# untitled.net
KiCad netlist of a schematic drawn in EAGLE
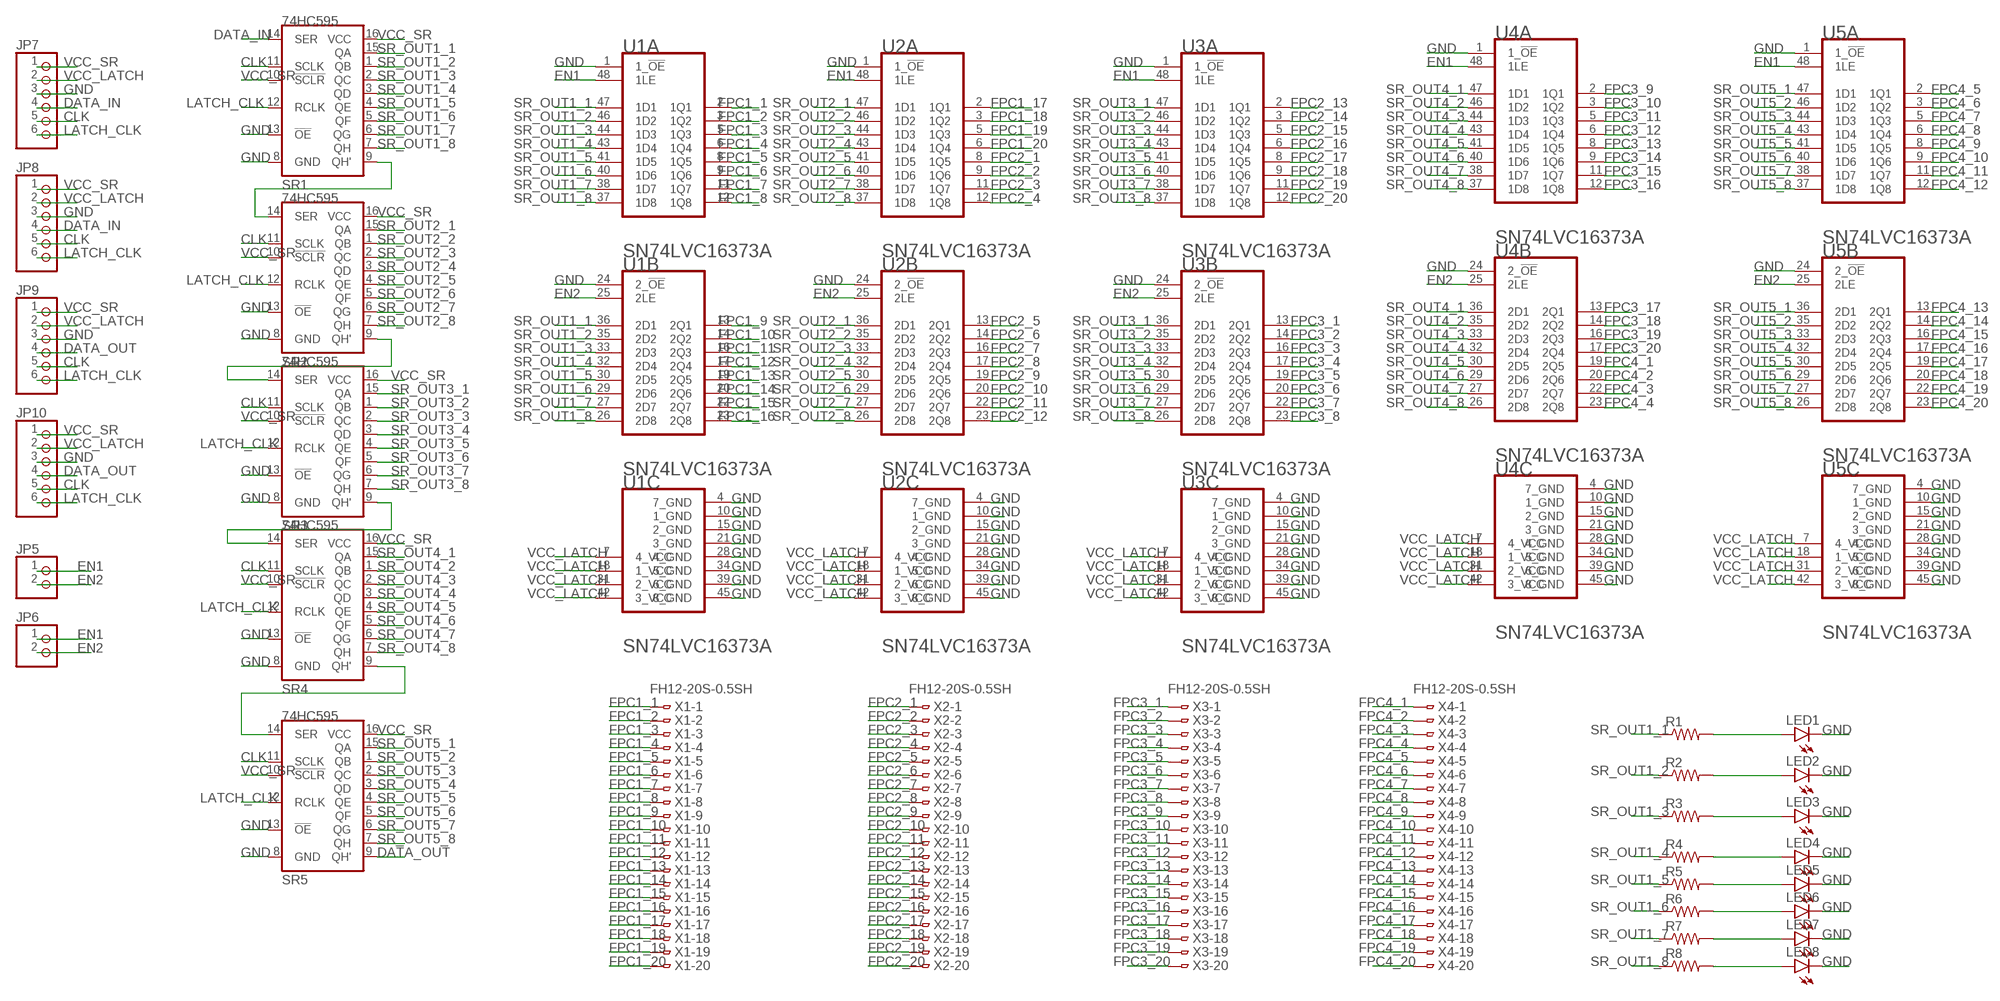
[diagram p0: schematic, sheet 1]

(export (version "E")
  (design (tool "Eeschema 10.0.6"))
  (components
    (comp (ref "JP5")
      (value "PINHD-1X2")
      (footprint "eagle-import:1X02")
      (libsource (lib "eagle-import") (part "PINHD-1X2"))
    )
    (comp (ref "JP6")
      (value "PINHD-1X2")
      (footprint "eagle-import:1X02")
      (libsource (lib "eagle-import") (part "PINHD-1X2"))
    )
    (comp (ref "JP7")
      (value "PINHD-1X6")
      (footprint "eagle-import:1X06")
      (libsource (lib "eagle-import") (part "PINHD-1X6"))
    )
    (comp (ref "JP8")
      (value "PINHD-1X6")
      (footprint "eagle-import:1X06")
      (libsource (lib "eagle-import") (part "PINHD-1X6"))
    )
    (comp (ref "JP9")
      (value "PINHD-1X6")
      (footprint "eagle-import:1X06")
      (libsource (lib "eagle-import") (part "PINHD-1X6"))
    )
    (comp (ref "JP10")
      (value "PINHD-1X6")
      (footprint "eagle-import:1X06")
      (libsource (lib "eagle-import") (part "PINHD-1X6"))
    )
    (comp (ref "LED1")
      (value "LEDCHIP-LED0805")
      (footprint "eagle-import:CHIP-LED0805")
      (libsource (lib "eagle-import") (part "LEDCHIP-LED0805"))
    )
    (comp (ref "LED2")
      (value "LEDCHIP-LED0805")
      (footprint "eagle-import:CHIP-LED0805")
      (libsource (lib "eagle-import") (part "LEDCHIP-LED0805"))
    )
    (comp (ref "LED3")
      (value "LEDCHIP-LED0805")
      (footprint "eagle-import:CHIP-LED0805")
      (libsource (lib "eagle-import") (part "LEDCHIP-LED0805"))
    )
    (comp (ref "LED4")
      (value "LEDCHIP-LED0805")
      (footprint "eagle-import:CHIP-LED0805")
      (libsource (lib "eagle-import") (part "LEDCHIP-LED0805"))
    )
    (comp (ref "LED5")
      (value "LEDCHIP-LED0805")
      (footprint "eagle-import:CHIP-LED0805")
      (libsource (lib "eagle-import") (part "LEDCHIP-LED0805"))
    )
    (comp (ref "LED6")
      (value "LEDCHIP-LED0805")
      (footprint "eagle-import:CHIP-LED0805")
      (libsource (lib "eagle-import") (part "LEDCHIP-LED0805"))
    )
    (comp (ref "LED7")
      (value "LEDCHIP-LED0805")
      (footprint "eagle-import:CHIP-LED0805")
      (libsource (lib "eagle-import") (part "LEDCHIP-LED0805"))
    )
    (comp (ref "LED8")
      (value "LEDCHIP-LED0805")
      (footprint "eagle-import:CHIP-LED0805")
      (libsource (lib "eagle-import") (part "LEDCHIP-LED0805"))
    )
    (comp (ref "R1")
      (value "R-US_R0805")
      (footprint "eagle-import:R0805")
      (libsource (lib "eagle-import") (part "R-US_R0805"))
    )
    (comp (ref "R2")
      (value "R-US_R0805")
      (footprint "eagle-import:R0805")
      (libsource (lib "eagle-import") (part "R-US_R0805"))
    )
    (comp (ref "R3")
      (value "R-US_R0805")
      (footprint "eagle-import:R0805")
      (libsource (lib "eagle-import") (part "R-US_R0805"))
    )
    (comp (ref "R4")
      (value "R-US_R0805")
      (footprint "eagle-import:R0805")
      (libsource (lib "eagle-import") (part "R-US_R0805"))
    )
    (comp (ref "R5")
      (value "R-US_R0805")
      (footprint "eagle-import:R0805")
      (libsource (lib "eagle-import") (part "R-US_R0805"))
    )
    (comp (ref "R6")
      (value "R-US_R0805")
      (footprint "eagle-import:R0805")
      (libsource (lib "eagle-import") (part "R-US_R0805"))
    )
    (comp (ref "R7")
      (value "R-US_R0805")
      (footprint "eagle-import:R0805")
      (libsource (lib "eagle-import") (part "R-US_R0805"))
    )
    (comp (ref "R8")
      (value "R-US_R0805")
      (footprint "eagle-import:R0805")
      (libsource (lib "eagle-import") (part "R-US_R0805"))
    )
    (comp (ref "SR1")
      (value "74HC595")
      (footprint "eagle-import:SO16")
      (fields (field (name "MF") "Nexperia"))
      (libsource (lib "eagle-import") (part "74HC595"))
    )
    (comp (ref "SR2")
      (value "74HC595")
      (footprint "eagle-import:SO16")
      (fields (field (name "MF") "Nexperia"))
      (libsource (lib "eagle-import") (part "74HC595"))
    )
    (comp (ref "SR3")
      (value "74HC595")
      (footprint "eagle-import:SO16")
      (fields (field (name "MF") "Nexperia"))
      (libsource (lib "eagle-import") (part "74HC595"))
    )
    (comp (ref "SR4")
      (value "74HC595")
      (footprint "eagle-import:SO16")
      (fields (field (name "MF") "Nexperia"))
      (libsource (lib "eagle-import") (part "74HC595"))
    )
    (comp (ref "SR5")
      (value "74HC595")
      (footprint "eagle-import:SO16")
      (fields (field (name "MF") "Nexperia"))
      (libsource (lib "eagle-import") (part "74HC595"))
    )
    (comp (ref "U1")
      (value "TEXAS_INSTRUMENTS_SN74LVC16373ATEXAS_INSTRUMENTS_SN74LVC16373A_0_2")
      (footprint "eagle-import:TEXAS_INSTRUMENTS_SN74LVC16373A_2")
      (fields (field (name "MF") "Texas Instruments") (field (name "MPN") "SN74LVC16373A"))
      (libsource (lib "eagle-import") (part "TEXAS_INSTRUMENTS_SN74LVC16373ATEXAS_INSTRUMENTS_SN74LVC16373A_0_2"))
    )
    (comp (ref "U2")
      (value "TEXAS_INSTRUMENTS_SN74LVC16373ATEXAS_INSTRUMENTS_SN74LVC16373A_0_2")
      (footprint "eagle-import:TEXAS_INSTRUMENTS_SN74LVC16373A_2")
      (fields (field (name "MF") "Texas Instruments") (field (name "MPN") "SN74LVC16373A"))
      (libsource (lib "eagle-import") (part "TEXAS_INSTRUMENTS_SN74LVC16373ATEXAS_INSTRUMENTS_SN74LVC16373A_0_2"))
    )
    (comp (ref "U3")
      (value "TEXAS_INSTRUMENTS_SN74LVC16373ATEXAS_INSTRUMENTS_SN74LVC16373A_0_2")
      (footprint "eagle-import:TEXAS_INSTRUMENTS_SN74LVC16373A_2")
      (fields (field (name "MF") "Texas Instruments") (field (name "MPN") "SN74LVC16373A"))
      (libsource (lib "eagle-import") (part "TEXAS_INSTRUMENTS_SN74LVC16373ATEXAS_INSTRUMENTS_SN74LVC16373A_0_2"))
    )
    (comp (ref "U4")
      (value "TEXAS_INSTRUMENTS_SN74LVC16373ATEXAS_INSTRUMENTS_SN74LVC16373A_0_2")
      (footprint "eagle-import:TEXAS_INSTRUMENTS_SN74LVC16373A_2")
      (fields (field (name "MF") "Texas Instruments") (field (name "MPN") "SN74LVC16373A"))
      (libsource (lib "eagle-import") (part "TEXAS_INSTRUMENTS_SN74LVC16373ATEXAS_INSTRUMENTS_SN74LVC16373A_0_2"))
    )
    (comp (ref "U5")
      (value "TEXAS_INSTRUMENTS_SN74LVC16373ATEXAS_INSTRUMENTS_SN74LVC16373A_0_2")
      (footprint "eagle-import:TEXAS_INSTRUMENTS_SN74LVC16373A_2")
      (fields (field (name "MF") "Texas Instruments") (field (name "MPN") "SN74LVC16373A"))
      (libsource (lib "eagle-import") (part "TEXAS_INSTRUMENTS_SN74LVC16373ATEXAS_INSTRUMENTS_SN74LVC16373A_0_2"))
    )
    (comp (ref "X1")
      (value "FH12-20S-0.5SH")
      (footprint "eagle-import:FH12-20S-0.5SH")
      (fields (field (name "MPN") "FH12-20S-0.5SH(55)"))
      (libsource (lib "eagle-import") (part "FH12-20S-0.5SH"))
    )
    (comp (ref "X2")
      (value "FH12-20S-0.5SH")
      (footprint "eagle-import:FH12-20S-0.5SH")
      (fields (field (name "MPN") "FH12-20S-0.5SH(55)"))
      (libsource (lib "eagle-import") (part "FH12-20S-0.5SH"))
    )
    (comp (ref "X3")
      (value "FH12-20S-0.5SH")
      (footprint "eagle-import:FH12-20S-0.5SH")
      (fields (field (name "MPN") "FH12-20S-0.5SH(55)"))
      (libsource (lib "eagle-import") (part "FH12-20S-0.5SH"))
    )
    (comp (ref "X4")
      (value "FH12-20S-0.5SH")
      (footprint "eagle-import:FH12-20S-0.5SH")
      (fields (field (name "MPN") "FH12-20S-0.5SH(55)"))
      (libsource (lib "eagle-import") (part "FH12-20S-0.5SH"))
    )
  )
  (nets
    (net (code "1") (name "/CLK") (class "Default")
      (node (ref "JP10") (pin "5") (pinfunction "5_5") (pintype "passive"))
      (node (ref "JP7") (pin "5") (pinfunction "5_5") (pintype "passive"))
      (node (ref "JP8") (pin "5") (pinfunction "5_5") (pintype "passive"))
      (node (ref "JP9") (pin "5") (pinfunction "5_5") (pintype "passive"))
      (node (ref "SR1") (pin "11") (pinfunction "SCLK_11") (pintype "input"))
      (node (ref "SR2") (pin "11") (pinfunction "SCLK_11") (pintype "input"))
      (node (ref "SR3") (pin "11") (pinfunction "SCLK_11") (pintype "input"))
      (node (ref "SR4") (pin "11") (pinfunction "SCLK_11") (pintype "input"))
      (node (ref "SR5") (pin "11") (pinfunction "SCLK_11") (pintype "input"))
    )
    (net (code "2") (name "/DATA_IN") (class "Default")
      (node (ref "JP7") (pin "4") (pinfunction "4_4") (pintype "passive"))
      (node (ref "JP8") (pin "4") (pinfunction "4_4") (pintype "passive"))
      (node (ref "SR1") (pin "14") (pinfunction "SER_14") (pintype "input"))
    )
    (net (code "3") (name "/DATA_OUT") (class "Default")
      (node (ref "JP10") (pin "4") (pinfunction "4_4") (pintype "passive"))
      (node (ref "JP9") (pin "4") (pinfunction "4_4") (pintype "passive"))
      (node (ref "SR5") (pin "9") (pinfunction "QH'_9") (pintype "tri_state"))
    )
    (net (code "4") (name "/EN1") (class "Default")
      (node (ref "JP5") (pin "1") (pinfunction "1_1") (pintype "passive"))
      (node (ref "JP6") (pin "1") (pinfunction "1_1") (pintype "passive"))
      (node (ref "U1") (pin "48") (pinfunction "1LE_48") (pintype "input"))
      (node (ref "U2") (pin "48") (pinfunction "1LE_48") (pintype "input"))
      (node (ref "U3") (pin "48") (pinfunction "1LE_48") (pintype "input"))
      (node (ref "U4") (pin "48") (pinfunction "1LE_48") (pintype "input"))
      (node (ref "U5") (pin "48") (pinfunction "1LE_48") (pintype "input"))
    )
    (net (code "5") (name "/EN2") (class "Default")
      (node (ref "JP5") (pin "2") (pinfunction "2_2") (pintype "passive"))
      (node (ref "JP6") (pin "2") (pinfunction "2_2") (pintype "passive"))
      (node (ref "U1") (pin "25") (pinfunction "2LE_25") (pintype "input"))
      (node (ref "U2") (pin "25") (pinfunction "2LE_25") (pintype "input"))
      (node (ref "U3") (pin "25") (pinfunction "2LE_25") (pintype "input"))
      (node (ref "U4") (pin "25") (pinfunction "2LE_25") (pintype "input"))
      (node (ref "U5") (pin "25") (pinfunction "2LE_25") (pintype "input"))
    )
    (net (code "6") (name "/FPC1_1") (class "Default")
      (node (ref "U1") (pin "2") (pinfunction "1Q1_2") (pintype "tri_state"))
      (node (ref "X1") (pin "1") (pinfunction "1_1") (pintype "passive"))
    )
    (net (code "7") (name "/FPC1_2") (class "Default")
      (node (ref "U1") (pin "3") (pinfunction "1Q2_3") (pintype "tri_state"))
      (node (ref "X1") (pin "2") (pinfunction "1_2") (pintype "passive"))
    )
    (net (code "8") (name "/FPC1_3") (class "Default")
      (node (ref "U1") (pin "5") (pinfunction "1Q3_5") (pintype "tri_state"))
      (node (ref "X1") (pin "3") (pinfunction "1_3") (pintype "passive"))
    )
    (net (code "9") (name "/FPC1_4") (class "Default")
      (node (ref "U1") (pin "6") (pinfunction "1Q4_6") (pintype "tri_state"))
      (node (ref "X1") (pin "4") (pinfunction "1_4") (pintype "passive"))
    )
    (net (code "10") (name "/FPC1_5") (class "Default")
      (node (ref "U1") (pin "8") (pinfunction "1Q5_8") (pintype "tri_state"))
      (node (ref "X1") (pin "5") (pinfunction "1_5") (pintype "passive"))
    )
    (net (code "11") (name "/FPC1_6") (class "Default")
      (node (ref "U1") (pin "9") (pinfunction "1Q6_9") (pintype "tri_state"))
      (node (ref "X1") (pin "6") (pinfunction "1_6") (pintype "passive"))
    )
    (net (code "12") (name "/FPC1_7") (class "Default")
      (node (ref "U1") (pin "11") (pinfunction "1Q7_11") (pintype "tri_state"))
      (node (ref "X1") (pin "7") (pinfunction "1_7") (pintype "passive"))
    )
    (net (code "13") (name "/FPC1_8") (class "Default")
      (node (ref "U1") (pin "12") (pinfunction "1Q8_12") (pintype "tri_state"))
      (node (ref "X1") (pin "8") (pinfunction "1_8") (pintype "passive"))
    )
    (net (code "14") (name "/FPC1_9") (class "Default")
      (node (ref "U1") (pin "13") (pinfunction "2Q1_13") (pintype "tri_state"))
      (node (ref "X1") (pin "9") (pinfunction "1_9") (pintype "passive"))
    )
    (net (code "15") (name "/FPC1_10") (class "Default")
      (node (ref "U1") (pin "14") (pinfunction "2Q2_14") (pintype "tri_state"))
      (node (ref "X1") (pin "10") (pinfunction "1_10") (pintype "passive"))
    )
    (net (code "16") (name "/FPC1_11") (class "Default")
      (node (ref "U1") (pin "16") (pinfunction "2Q3_16") (pintype "tri_state"))
      (node (ref "X1") (pin "11") (pinfunction "1_11") (pintype "passive"))
    )
    (net (code "17") (name "/FPC1_12") (class "Default")
      (node (ref "U1") (pin "17") (pinfunction "2Q4_17") (pintype "tri_state"))
      (node (ref "X1") (pin "12") (pinfunction "1_12") (pintype "passive"))
    )
    (net (code "18") (name "/FPC1_13") (class "Default")
      (node (ref "U1") (pin "19") (pinfunction "2Q5_19") (pintype "tri_state"))
      (node (ref "X1") (pin "13") (pinfunction "1_13") (pintype "passive"))
    )
    (net (code "19") (name "/FPC1_14") (class "Default")
      (node (ref "U1") (pin "20") (pinfunction "2Q6_20") (pintype "tri_state"))
      (node (ref "X1") (pin "14") (pinfunction "1_14") (pintype "passive"))
    )
    (net (code "20") (name "/FPC1_15") (class "Default")
      (node (ref "U1") (pin "22") (pinfunction "2Q7_22") (pintype "tri_state"))
      (node (ref "X1") (pin "15") (pinfunction "1_15") (pintype "passive"))
    )
    (net (code "21") (name "/FPC1_16") (class "Default")
      (node (ref "U1") (pin "23") (pinfunction "2Q8_23") (pintype "tri_state"))
      (node (ref "X1") (pin "16") (pinfunction "1_16") (pintype "passive"))
    )
    (net (code "22") (name "/FPC1_17") (class "Default")
      (node (ref "U2") (pin "2") (pinfunction "1Q1_2") (pintype "tri_state"))
      (node (ref "X1") (pin "17") (pinfunction "1_17") (pintype "passive"))
    )
    (net (code "23") (name "/FPC1_18") (class "Default")
      (node (ref "U2") (pin "3") (pinfunction "1Q2_3") (pintype "tri_state"))
      (node (ref "X1") (pin "18") (pinfunction "1_18") (pintype "passive"))
    )
    (net (code "24") (name "/FPC1_19") (class "Default")
      (node (ref "U2") (pin "5") (pinfunction "1Q3_5") (pintype "tri_state"))
      (node (ref "X1") (pin "19") (pinfunction "1_19") (pintype "passive"))
    )
    (net (code "25") (name "/FPC1_20") (class "Default")
      (node (ref "U2") (pin "6") (pinfunction "1Q4_6") (pintype "tri_state"))
      (node (ref "X1") (pin "20") (pinfunction "1_20") (pintype "passive"))
    )
    (net (code "26") (name "/FPC2_1") (class "Default")
      (node (ref "U2") (pin "8") (pinfunction "1Q5_8") (pintype "tri_state"))
      (node (ref "X2") (pin "1") (pinfunction "1_1") (pintype "passive"))
    )
    (net (code "27") (name "/FPC2_2") (class "Default")
      (node (ref "U2") (pin "9") (pinfunction "1Q6_9") (pintype "tri_state"))
      (node (ref "X2") (pin "2") (pinfunction "1_2") (pintype "passive"))
    )
    (net (code "28") (name "/FPC2_3") (class "Default")
      (node (ref "U2") (pin "11") (pinfunction "1Q7_11") (pintype "tri_state"))
      (node (ref "X2") (pin "3") (pinfunction "1_3") (pintype "passive"))
    )
    (net (code "29") (name "/FPC2_4") (class "Default")
      (node (ref "U2") (pin "12") (pinfunction "1Q8_12") (pintype "tri_state"))
      (node (ref "X2") (pin "4") (pinfunction "1_4") (pintype "passive"))
    )
    (net (code "30") (name "/FPC2_5") (class "Default")
      (node (ref "U2") (pin "13") (pinfunction "2Q1_13") (pintype "tri_state"))
      (node (ref "X2") (pin "5") (pinfunction "1_5") (pintype "passive"))
    )
    (net (code "31") (name "/FPC2_6") (class "Default")
      (node (ref "U2") (pin "14") (pinfunction "2Q2_14") (pintype "tri_state"))
      (node (ref "X2") (pin "6") (pinfunction "1_6") (pintype "passive"))
    )
    (net (code "32") (name "/FPC2_7") (class "Default")
      (node (ref "U2") (pin "16") (pinfunction "2Q3_16") (pintype "tri_state"))
      (node (ref "X2") (pin "7") (pinfunction "1_7") (pintype "passive"))
    )
    (net (code "33") (name "/FPC2_8") (class "Default")
      (node (ref "U2") (pin "17") (pinfunction "2Q4_17") (pintype "tri_state"))
      (node (ref "X2") (pin "8") (pinfunction "1_8") (pintype "passive"))
    )
    (net (code "34") (name "/FPC2_9") (class "Default")
      (node (ref "U2") (pin "19") (pinfunction "2Q5_19") (pintype "tri_state"))
      (node (ref "X2") (pin "9") (pinfunction "1_9") (pintype "passive"))
    )
    (net (code "35") (name "/FPC2_10") (class "Default")
      (node (ref "U2") (pin "20") (pinfunction "2Q6_20") (pintype "tri_state"))
      (node (ref "X2") (pin "10") (pinfunction "1_10") (pintype "passive"))
    )
    (net (code "36") (name "/FPC2_11") (class "Default")
      (node (ref "U2") (pin "22") (pinfunction "2Q7_22") (pintype "tri_state"))
      (node (ref "X2") (pin "11") (pinfunction "1_11") (pintype "passive"))
    )
    (net (code "37") (name "/FPC2_12") (class "Default")
      (node (ref "U2") (pin "23") (pinfunction "2Q8_23") (pintype "tri_state"))
      (node (ref "X2") (pin "12") (pinfunction "1_12") (pintype "passive"))
    )
    (net (code "38") (name "/FPC2_13") (class "Default")
      (node (ref "U3") (pin "2") (pinfunction "1Q1_2") (pintype "tri_state"))
      (node (ref "X2") (pin "13") (pinfunction "1_13") (pintype "passive"))
    )
    (net (code "39") (name "/FPC2_14") (class "Default")
      (node (ref "U3") (pin "3") (pinfunction "1Q2_3") (pintype "tri_state"))
      (node (ref "X2") (pin "14") (pinfunction "1_14") (pintype "passive"))
    )
    (net (code "40") (name "/FPC2_15") (class "Default")
      (node (ref "U3") (pin "5") (pinfunction "1Q3_5") (pintype "tri_state"))
      (node (ref "X2") (pin "15") (pinfunction "1_15") (pintype "passive"))
    )
    (net (code "41") (name "/FPC2_16") (class "Default")
      (node (ref "U3") (pin "6") (pinfunction "1Q4_6") (pintype "tri_state"))
      (node (ref "X2") (pin "16") (pinfunction "1_16") (pintype "passive"))
    )
    (net (code "42") (name "/FPC2_17") (class "Default")
      (node (ref "U3") (pin "8") (pinfunction "1Q5_8") (pintype "tri_state"))
      (node (ref "X2") (pin "17") (pinfunction "1_17") (pintype "passive"))
    )
    (net (code "43") (name "/FPC2_18") (class "Default")
      (node (ref "U3") (pin "9") (pinfunction "1Q6_9") (pintype "tri_state"))
      (node (ref "X2") (pin "18") (pinfunction "1_18") (pintype "passive"))
    )
    (net (code "44") (name "/FPC2_19") (class "Default")
      (node (ref "U3") (pin "11") (pinfunction "1Q7_11") (pintype "tri_state"))
      (node (ref "X2") (pin "19") (pinfunction "1_19") (pintype "passive"))
    )
    (net (code "45") (name "/FPC2_20") (class "Default")
      (node (ref "U3") (pin "12") (pinfunction "1Q8_12") (pintype "tri_state"))
      (node (ref "X2") (pin "20") (pinfunction "1_20") (pintype "passive"))
    )
    (net (code "46") (name "/FPC3_1") (class "Default")
      (node (ref "U3") (pin "13") (pinfunction "2Q1_13") (pintype "tri_state"))
      (node (ref "X3") (pin "1") (pinfunction "1_1") (pintype "passive"))
    )
    (net (code "47") (name "/FPC3_2") (class "Default")
      (node (ref "U3") (pin "14") (pinfunction "2Q2_14") (pintype "tri_state"))
      (node (ref "X3") (pin "2") (pinfunction "1_2") (pintype "passive"))
    )
    (net (code "48") (name "/FPC3_3") (class "Default")
      (node (ref "U3") (pin "16") (pinfunction "2Q3_16") (pintype "tri_state"))
      (node (ref "X3") (pin "3") (pinfunction "1_3") (pintype "passive"))
    )
    (net (code "49") (name "/FPC3_4") (class "Default")
      (node (ref "U3") (pin "17") (pinfunction "2Q4_17") (pintype "tri_state"))
      (node (ref "X3") (pin "4") (pinfunction "1_4") (pintype "passive"))
    )
    (net (code "50") (name "/FPC3_5") (class "Default")
      (node (ref "U3") (pin "19") (pinfunction "2Q5_19") (pintype "tri_state"))
      (node (ref "X3") (pin "5") (pinfunction "1_5") (pintype "passive"))
    )
    (net (code "51") (name "/FPC3_6") (class "Default")
      (node (ref "U3") (pin "20") (pinfunction "2Q6_20") (pintype "tri_state"))
      (node (ref "X3") (pin "6") (pinfunction "1_6") (pintype "passive"))
    )
    (net (code "52") (name "/FPC3_7") (class "Default")
      (node (ref "U3") (pin "22") (pinfunction "2Q7_22") (pintype "tri_state"))
      (node (ref "X3") (pin "7") (pinfunction "1_7") (pintype "passive"))
    )
    (net (code "53") (name "/FPC3_8") (class "Default")
      (node (ref "U3") (pin "23") (pinfunction "2Q8_23") (pintype "tri_state"))
      (node (ref "X3") (pin "8") (pinfunction "1_8") (pintype "passive"))
    )
    (net (code "54") (name "/FPC3_9") (class "Default")
      (node (ref "U4") (pin "2") (pinfunction "1Q1_2") (pintype "tri_state"))
      (node (ref "X3") (pin "9") (pinfunction "1_9") (pintype "passive"))
    )
    (net (code "55") (name "/FPC3_10") (class "Default")
      (node (ref "U4") (pin "3") (pinfunction "1Q2_3") (pintype "tri_state"))
      (node (ref "X3") (pin "10") (pinfunction "1_10") (pintype "passive"))
    )
    (net (code "56") (name "/FPC3_11") (class "Default")
      (node (ref "U4") (pin "5") (pinfunction "1Q3_5") (pintype "tri_state"))
      (node (ref "X3") (pin "11") (pinfunction "1_11") (pintype "passive"))
    )
    (net (code "57") (name "/FPC3_12") (class "Default")
      (node (ref "U4") (pin "6") (pinfunction "1Q4_6") (pintype "tri_state"))
      (node (ref "X3") (pin "12") (pinfunction "1_12") (pintype "passive"))
    )
    (net (code "58") (name "/FPC3_13") (class "Default")
      (node (ref "U4") (pin "8") (pinfunction "1Q5_8") (pintype "tri_state"))
      (node (ref "X3") (pin "13") (pinfunction "1_13") (pintype "passive"))
    )
    (net (code "59") (name "/FPC3_14") (class "Default")
      (node (ref "U4") (pin "9") (pinfunction "1Q6_9") (pintype "tri_state"))
      (node (ref "X3") (pin "14") (pinfunction "1_14") (pintype "passive"))
    )
    (net (code "60") (name "/FPC3_15") (class "Default")
      (node (ref "U4") (pin "11") (pinfunction "1Q7_11") (pintype "tri_state"))
      (node (ref "X3") (pin "15") (pinfunction "1_15") (pintype "passive"))
    )
    (net (code "61") (name "/FPC3_16") (class "Default")
      (node (ref "U4") (pin "12") (pinfunction "1Q8_12") (pintype "tri_state"))
      (node (ref "X3") (pin "16") (pinfunction "1_16") (pintype "passive"))
    )
    (net (code "62") (name "/FPC3_17") (class "Default")
      (node (ref "U4") (pin "13") (pinfunction "2Q1_13") (pintype "tri_state"))
      (node (ref "X3") (pin "17") (pinfunction "1_17") (pintype "passive"))
    )
    (net (code "63") (name "/FPC3_18") (class "Default")
      (node (ref "U4") (pin "14") (pinfunction "2Q2_14") (pintype "tri_state"))
      (node (ref "X3") (pin "18") (pinfunction "1_18") (pintype "passive"))
    )
    (net (code "64") (name "/FPC3_19") (class "Default")
      (node (ref "U4") (pin "16") (pinfunction "2Q3_16") (pintype "tri_state"))
      (node (ref "X3") (pin "19") (pinfunction "1_19") (pintype "passive"))
    )
    (net (code "65") (name "/FPC3_20") (class "Default")
      (node (ref "U4") (pin "17") (pinfunction "2Q4_17") (pintype "tri_state"))
      (node (ref "X3") (pin "20") (pinfunction "1_20") (pintype "passive"))
    )
    (net (code "66") (name "/FPC4_1") (class "Default")
      (node (ref "U4") (pin "19") (pinfunction "2Q5_19") (pintype "tri_state"))
      (node (ref "X4") (pin "1") (pinfunction "1_1") (pintype "passive"))
    )
    (net (code "67") (name "/FPC4_2") (class "Default")
      (node (ref "U4") (pin "20") (pinfunction "2Q6_20") (pintype "tri_state"))
      (node (ref "X4") (pin "2") (pinfunction "1_2") (pintype "passive"))
    )
    (net (code "68") (name "/FPC4_3") (class "Default")
      (node (ref "U4") (pin "22") (pinfunction "2Q7_22") (pintype "tri_state"))
      (node (ref "X4") (pin "3") (pinfunction "1_3") (pintype "passive"))
    )
    (net (code "69") (name "/FPC4_4") (class "Default")
      (node (ref "U4") (pin "23") (pinfunction "2Q8_23") (pintype "tri_state"))
      (node (ref "X4") (pin "4") (pinfunction "1_4") (pintype "passive"))
    )
    (net (code "70") (name "/FPC4_5") (class "Default")
      (node (ref "U5") (pin "2") (pinfunction "1Q1_2") (pintype "tri_state"))
      (node (ref "X4") (pin "5") (pinfunction "1_5") (pintype "passive"))
    )
    (net (code "71") (name "/FPC4_6") (class "Default")
      (node (ref "U5") (pin "3") (pinfunction "1Q2_3") (pintype "tri_state"))
      (node (ref "X4") (pin "6") (pinfunction "1_6") (pintype "passive"))
    )
    (net (code "72") (name "/FPC4_7") (class "Default")
      (node (ref "U5") (pin "5") (pinfunction "1Q3_5") (pintype "tri_state"))
      (node (ref "X4") (pin "7") (pinfunction "1_7") (pintype "passive"))
    )
    (net (code "73") (name "/FPC4_8") (class "Default")
      (node (ref "U5") (pin "6") (pinfunction "1Q4_6") (pintype "tri_state"))
      (node (ref "X4") (pin "8") (pinfunction "1_8") (pintype "passive"))
    )
    (net (code "74") (name "/FPC4_9") (class "Default")
      (node (ref "U5") (pin "8") (pinfunction "1Q5_8") (pintype "tri_state"))
      (node (ref "X4") (pin "9") (pinfunction "1_9") (pintype "passive"))
    )
    (net (code "75") (name "/FPC4_10") (class "Default")
      (node (ref "U5") (pin "9") (pinfunction "1Q6_9") (pintype "tri_state"))
      (node (ref "X4") (pin "10") (pinfunction "1_10") (pintype "passive"))
    )
    (net (code "76") (name "/FPC4_11") (class "Default")
      (node (ref "U5") (pin "11") (pinfunction "1Q7_11") (pintype "tri_state"))
      (node (ref "X4") (pin "11") (pinfunction "1_11") (pintype "passive"))
    )
    (net (code "77") (name "/FPC4_12") (class "Default")
      (node (ref "U5") (pin "12") (pinfunction "1Q8_12") (pintype "tri_state"))
      (node (ref "X4") (pin "12") (pinfunction "1_12") (pintype "passive"))
    )
    (net (code "78") (name "/FPC4_13") (class "Default")
      (node (ref "U5") (pin "13") (pinfunction "2Q1_13") (pintype "tri_state"))
      (node (ref "X4") (pin "13") (pinfunction "1_13") (pintype "passive"))
    )
    (net (code "79") (name "/FPC4_14") (class "Default")
      (node (ref "U5") (pin "14") (pinfunction "2Q2_14") (pintype "tri_state"))
      (node (ref "X4") (pin "14") (pinfunction "1_14") (pintype "passive"))
    )
    (net (code "80") (name "/FPC4_15") (class "Default")
      (node (ref "U5") (pin "16") (pinfunction "2Q3_16") (pintype "tri_state"))
      (node (ref "X4") (pin "15") (pinfunction "1_15") (pintype "passive"))
    )
    (net (code "81") (name "/FPC4_16") (class "Default")
      (node (ref "U5") (pin "17") (pinfunction "2Q4_17") (pintype "tri_state"))
      (node (ref "X4") (pin "16") (pinfunction "1_16") (pintype "passive"))
    )
    (net (code "82") (name "/FPC4_17") (class "Default")
      (node (ref "U5") (pin "19") (pinfunction "2Q5_19") (pintype "tri_state"))
      (node (ref "X4") (pin "17") (pinfunction "1_17") (pintype "passive"))
    )
    (net (code "83") (name "/FPC4_18") (class "Default")
      (node (ref "U5") (pin "20") (pinfunction "2Q6_20") (pintype "tri_state"))
      (node (ref "X4") (pin "18") (pinfunction "1_18") (pintype "passive"))
    )
    (net (code "84") (name "/FPC4_19") (class "Default")
      (node (ref "U5") (pin "22") (pinfunction "2Q7_22") (pintype "tri_state"))
      (node (ref "X4") (pin "19") (pinfunction "1_19") (pintype "passive"))
    )
    (net (code "85") (name "/FPC4_20") (class "Default")
      (node (ref "U5") (pin "23") (pinfunction "2Q8_23") (pintype "tri_state"))
      (node (ref "X4") (pin "20") (pinfunction "1_20") (pintype "passive"))
    )
    (net (code "86") (name "/GND") (class "Default")
      (node (ref "JP10") (pin "3") (pinfunction "3_3") (pintype "passive"))
      (node (ref "JP7") (pin "3") (pinfunction "3_3") (pintype "passive"))
      (node (ref "JP8") (pin "3") (pinfunction "3_3") (pintype "passive"))
      (node (ref "JP9") (pin "3") (pinfunction "3_3") (pintype "passive"))
      (node (ref "LED1") (pin "C") (pinfunction "C_C") (pintype "passive"))
      (node (ref "LED2") (pin "C") (pinfunction "C_C") (pintype "passive"))
      (node (ref "LED3") (pin "C") (pinfunction "C_C") (pintype "passive"))
      (node (ref "LED4") (pin "C") (pinfunction "C_C") (pintype "passive"))
      (node (ref "LED5") (pin "C") (pinfunction "C_C") (pintype "passive"))
      (node (ref "LED6") (pin "C") (pinfunction "C_C") (pintype "passive"))
      (node (ref "LED7") (pin "C") (pinfunction "C_C") (pintype "passive"))
      (node (ref "LED8") (pin "C") (pinfunction "C_C") (pintype "passive"))
      (node (ref "SR1") (pin "13") (pinfunction "~{OE}_13") (pintype "input"))
      (node (ref "SR1") (pin "8") (pinfunction "GND_8") (pintype "power_in"))
      (node (ref "SR2") (pin "13") (pinfunction "~{OE}_13") (pintype "input"))
      (node (ref "SR2") (pin "8") (pinfunction "GND_8") (pintype "power_in"))
      (node (ref "SR3") (pin "13") (pinfunction "~{OE}_13") (pintype "input"))
      (node (ref "SR3") (pin "8") (pinfunction "GND_8") (pintype "power_in"))
      (node (ref "SR4") (pin "13") (pinfunction "~{OE}_13") (pintype "input"))
      (node (ref "SR4") (pin "8") (pinfunction "GND_8") (pintype "power_in"))
      (node (ref "SR5") (pin "13") (pinfunction "~{OE}_13") (pintype "input"))
      (node (ref "SR5") (pin "8") (pinfunction "GND_8") (pintype "power_in"))
      (node (ref "U1") (pin "1") (pinfunction "1_~{OE}_1") (pintype "input"))
      (node (ref "U1") (pin "10") (pinfunction "1_GND_10") (pintype "power_in"))
      (node (ref "U1") (pin "15") (pinfunction "2_GND_15") (pintype "power_in"))
      (node (ref "U1") (pin "21") (pinfunction "3_GND_21") (pintype "power_in"))
      (node (ref "U1") (pin "24") (pinfunction "2_~{OE}_24") (pintype "input"))
      (node (ref "U1") (pin "28") (pinfunction "4_GND_28") (pintype "power_in"))
      (node (ref "U1") (pin "34") (pinfunction "5_GND_34") (pintype "power_in"))
      (node (ref "U1") (pin "39") (pinfunction "6_GND_39") (pintype "power_in"))
      (node (ref "U1") (pin "4") (pinfunction "7_GND_4") (pintype "power_in"))
      (node (ref "U1") (pin "45") (pinfunction "8_GND_45") (pintype "power_in"))
      (node (ref "U2") (pin "1") (pinfunction "1_~{OE}_1") (pintype "input"))
      (node (ref "U2") (pin "10") (pinfunction "1_GND_10") (pintype "power_in"))
      (node (ref "U2") (pin "15") (pinfunction "2_GND_15") (pintype "power_in"))
      (node (ref "U2") (pin "21") (pinfunction "3_GND_21") (pintype "power_in"))
      (node (ref "U2") (pin "24") (pinfunction "2_~{OE}_24") (pintype "input"))
      (node (ref "U2") (pin "28") (pinfunction "4_GND_28") (pintype "power_in"))
      (node (ref "U2") (pin "34") (pinfunction "5_GND_34") (pintype "power_in"))
      (node (ref "U2") (pin "39") (pinfunction "6_GND_39") (pintype "power_in"))
      (node (ref "U2") (pin "4") (pinfunction "7_GND_4") (pintype "power_in"))
      (node (ref "U2") (pin "45") (pinfunction "8_GND_45") (pintype "power_in"))
      (node (ref "U3") (pin "1") (pinfunction "1_~{OE}_1") (pintype "input"))
      (node (ref "U3") (pin "10") (pinfunction "1_GND_10") (pintype "power_in"))
      (node (ref "U3") (pin "15") (pinfunction "2_GND_15") (pintype "power_in"))
      (node (ref "U3") (pin "21") (pinfunction "3_GND_21") (pintype "power_in"))
      (node (ref "U3") (pin "24") (pinfunction "2_~{OE}_24") (pintype "input"))
      (node (ref "U3") (pin "28") (pinfunction "4_GND_28") (pintype "power_in"))
      (node (ref "U3") (pin "34") (pinfunction "5_GND_34") (pintype "power_in"))
      (node (ref "U3") (pin "39") (pinfunction "6_GND_39") (pintype "power_in"))
      (node (ref "U3") (pin "4") (pinfunction "7_GND_4") (pintype "power_in"))
      (node (ref "U3") (pin "45") (pinfunction "8_GND_45") (pintype "power_in"))
      (node (ref "U4") (pin "1") (pinfunction "1_~{OE}_1") (pintype "input"))
      (node (ref "U4") (pin "10") (pinfunction "1_GND_10") (pintype "power_in"))
      (node (ref "U4") (pin "15") (pinfunction "2_GND_15") (pintype "power_in"))
      (node (ref "U4") (pin "21") (pinfunction "3_GND_21") (pintype "power_in"))
      (node (ref "U4") (pin "24") (pinfunction "2_~{OE}_24") (pintype "input"))
      (node (ref "U4") (pin "28") (pinfunction "4_GND_28") (pintype "power_in"))
      (node (ref "U4") (pin "34") (pinfunction "5_GND_34") (pintype "power_in"))
      (node (ref "U4") (pin "39") (pinfunction "6_GND_39") (pintype "power_in"))
      (node (ref "U4") (pin "4") (pinfunction "7_GND_4") (pintype "power_in"))
      (node (ref "U4") (pin "45") (pinfunction "8_GND_45") (pintype "power_in"))
      (node (ref "U5") (pin "1") (pinfunction "1_~{OE}_1") (pintype "input"))
      (node (ref "U5") (pin "10") (pinfunction "1_GND_10") (pintype "power_in"))
      (node (ref "U5") (pin "15") (pinfunction "2_GND_15") (pintype "power_in"))
      (node (ref "U5") (pin "21") (pinfunction "3_GND_21") (pintype "power_in"))
      (node (ref "U5") (pin "24") (pinfunction "2_~{OE}_24") (pintype "input"))
      (node (ref "U5") (pin "28") (pinfunction "4_GND_28") (pintype "power_in"))
      (node (ref "U5") (pin "34") (pinfunction "5_GND_34") (pintype "power_in"))
      (node (ref "U5") (pin "39") (pinfunction "6_GND_39") (pintype "power_in"))
      (node (ref "U5") (pin "4") (pinfunction "7_GND_4") (pintype "power_in"))
      (node (ref "U5") (pin "45") (pinfunction "8_GND_45") (pintype "power_in"))
    )
    (net (code "87") (name "/LATCH_CLK") (class "Default")
      (node (ref "JP10") (pin "6") (pinfunction "6_6") (pintype "passive"))
      (node (ref "JP7") (pin "6") (pinfunction "6_6") (pintype "passive"))
      (node (ref "JP8") (pin "6") (pinfunction "6_6") (pintype "passive"))
      (node (ref "JP9") (pin "6") (pinfunction "6_6") (pintype "passive"))
      (node (ref "SR1") (pin "12") (pinfunction "RCLK_12") (pintype "input"))
      (node (ref "SR2") (pin "12") (pinfunction "RCLK_12") (pintype "input"))
      (node (ref "SR3") (pin "12") (pinfunction "RCLK_12") (pintype "input"))
      (node (ref "SR4") (pin "12") (pinfunction "RCLK_12") (pintype "input"))
      (node (ref "SR5") (pin "12") (pinfunction "RCLK_12") (pintype "input"))
    )
    (net (code "88") (name "/SR_OUT1_1") (class "Default")
      (node (ref "R1") (pin "1") (pinfunction "1_1") (pintype "passive"))
      (node (ref "SR1") (pin "15") (pinfunction "QA_15") (pintype "tri_state"))
      (node (ref "U1") (pin "36") (pinfunction "2D1_36") (pintype "input"))
      (node (ref "U1") (pin "47") (pinfunction "1D1_47") (pintype "input"))
    )
    (net (code "89") (name "/SR_OUT1_2") (class "Default")
      (node (ref "R2") (pin "1") (pinfunction "1_1") (pintype "passive"))
      (node (ref "SR1") (pin "1") (pinfunction "QB_1") (pintype "tri_state"))
      (node (ref "U1") (pin "35") (pinfunction "2D2_35") (pintype "input"))
      (node (ref "U1") (pin "46") (pinfunction "1D2_46") (pintype "input"))
    )
    (net (code "90") (name "/SR_OUT1_3") (class "Default")
      (node (ref "R3") (pin "1") (pinfunction "1_1") (pintype "passive"))
      (node (ref "SR1") (pin "2") (pinfunction "QC_2") (pintype "tri_state"))
      (node (ref "U1") (pin "33") (pinfunction "2D3_33") (pintype "input"))
      (node (ref "U1") (pin "44") (pinfunction "1D3_44") (pintype "input"))
    )
    (net (code "91") (name "/SR_OUT1_4") (class "Default")
      (node (ref "R4") (pin "1") (pinfunction "1_1") (pintype "passive"))
      (node (ref "SR1") (pin "3") (pinfunction "QD_3") (pintype "tri_state"))
      (node (ref "U1") (pin "32") (pinfunction "2D4_32") (pintype "input"))
      (node (ref "U1") (pin "43") (pinfunction "1D4_43") (pintype "input"))
    )
    (net (code "92") (name "/SR_OUT1_5") (class "Default")
      (node (ref "R5") (pin "1") (pinfunction "1_1") (pintype "passive"))
      (node (ref "SR1") (pin "4") (pinfunction "QE_4") (pintype "tri_state"))
      (node (ref "U1") (pin "30") (pinfunction "2D5_30") (pintype "input"))
      (node (ref "U1") (pin "41") (pinfunction "1D5_41") (pintype "input"))
    )
    (net (code "93") (name "/SR_OUT1_6") (class "Default")
      (node (ref "R6") (pin "1") (pinfunction "1_1") (pintype "passive"))
      (node (ref "SR1") (pin "5") (pinfunction "QF_5") (pintype "tri_state"))
      (node (ref "U1") (pin "29") (pinfunction "2D6_29") (pintype "input"))
      (node (ref "U1") (pin "40") (pinfunction "1D6_40") (pintype "input"))
    )
    (net (code "94") (name "/SR_OUT1_7") (class "Default")
      (node (ref "R7") (pin "1") (pinfunction "1_1") (pintype "passive"))
      (node (ref "SR1") (pin "6") (pinfunction "QG_6") (pintype "tri_state"))
      (node (ref "U1") (pin "27") (pinfunction "2D7_27") (pintype "input"))
      (node (ref "U1") (pin "38") (pinfunction "1D7_38") (pintype "input"))
    )
    (net (code "95") (name "/SR_OUT1_8") (class "Default")
      (node (ref "R8") (pin "1") (pinfunction "1_1") (pintype "passive"))
      (node (ref "SR1") (pin "7") (pinfunction "QH_7") (pintype "tri_state"))
      (node (ref "U1") (pin "26") (pinfunction "2D8_26") (pintype "input"))
      (node (ref "U1") (pin "37") (pinfunction "1D8_37") (pintype "input"))
    )
    (net (code "96") (name "/SR_OUT2_1") (class "Default")
      (node (ref "SR2") (pin "15") (pinfunction "QA_15") (pintype "tri_state"))
      (node (ref "U2") (pin "36") (pinfunction "2D1_36") (pintype "input"))
      (node (ref "U2") (pin "47") (pinfunction "1D1_47") (pintype "input"))
    )
    (net (code "97") (name "/SR_OUT2_2") (class "Default")
      (node (ref "SR2") (pin "1") (pinfunction "QB_1") (pintype "tri_state"))
      (node (ref "U2") (pin "35") (pinfunction "2D2_35") (pintype "input"))
      (node (ref "U2") (pin "46") (pinfunction "1D2_46") (pintype "input"))
    )
    (net (code "98") (name "/SR_OUT2_3") (class "Default")
      (node (ref "SR2") (pin "2") (pinfunction "QC_2") (pintype "tri_state"))
      (node (ref "U2") (pin "33") (pinfunction "2D3_33") (pintype "input"))
      (node (ref "U2") (pin "44") (pinfunction "1D3_44") (pintype "input"))
    )
    (net (code "99") (name "/SR_OUT2_4") (class "Default")
      (node (ref "SR2") (pin "3") (pinfunction "QD_3") (pintype "tri_state"))
      (node (ref "U2") (pin "32") (pinfunction "2D4_32") (pintype "input"))
      (node (ref "U2") (pin "43") (pinfunction "1D4_43") (pintype "input"))
    )
    (net (code "100") (name "/SR_OUT2_5") (class "Default")
      (node (ref "SR2") (pin "4") (pinfunction "QE_4") (pintype "tri_state"))
      (node (ref "U2") (pin "30") (pinfunction "2D5_30") (pintype "input"))
      (node (ref "U2") (pin "41") (pinfunction "1D5_41") (pintype "input"))
    )
    (net (code "101") (name "/SR_OUT2_6") (class "Default")
      (node (ref "SR2") (pin "5") (pinfunction "QF_5") (pintype "tri_state"))
      (node (ref "U2") (pin "29") (pinfunction "2D6_29") (pintype "input"))
      (node (ref "U2") (pin "40") (pinfunction "1D6_40") (pintype "input"))
    )
    (net (code "102") (name "/SR_OUT2_7") (class "Default")
      (node (ref "SR2") (pin "6") (pinfunction "QG_6") (pintype "tri_state"))
      (node (ref "U2") (pin "27") (pinfunction "2D7_27") (pintype "input"))
      (node (ref "U2") (pin "38") (pinfunction "1D7_38") (pintype "input"))
    )
    (net (code "103") (name "/SR_OUT2_8") (class "Default")
      (node (ref "SR2") (pin "7") (pinfunction "QH_7") (pintype "tri_state"))
      (node (ref "U2") (pin "26") (pinfunction "2D8_26") (pintype "input"))
      (node (ref "U2") (pin "37") (pinfunction "1D8_37") (pintype "input"))
    )
    (net (code "104") (name "/SR_OUT3_1") (class "Default")
      (node (ref "SR3") (pin "15") (pinfunction "QA_15") (pintype "tri_state"))
      (node (ref "U3") (pin "36") (pinfunction "2D1_36") (pintype "input"))
      (node (ref "U3") (pin "47") (pinfunction "1D1_47") (pintype "input"))
    )
    (net (code "105") (name "/SR_OUT3_2") (class "Default")
      (node (ref "SR3") (pin "1") (pinfunction "QB_1") (pintype "tri_state"))
      (node (ref "U3") (pin "35") (pinfunction "2D2_35") (pintype "input"))
      (node (ref "U3") (pin "46") (pinfunction "1D2_46") (pintype "input"))
    )
    (net (code "106") (name "/SR_OUT3_3") (class "Default")
      (node (ref "SR3") (pin "2") (pinfunction "QC_2") (pintype "tri_state"))
      (node (ref "U3") (pin "33") (pinfunction "2D3_33") (pintype "input"))
      (node (ref "U3") (pin "44") (pinfunction "1D3_44") (pintype "input"))
    )
    (net (code "107") (name "/SR_OUT3_4") (class "Default")
      (node (ref "SR3") (pin "3") (pinfunction "QD_3") (pintype "tri_state"))
      (node (ref "U3") (pin "32") (pinfunction "2D4_32") (pintype "input"))
      (node (ref "U3") (pin "43") (pinfunction "1D4_43") (pintype "input"))
    )
    (net (code "108") (name "/SR_OUT3_5") (class "Default")
      (node (ref "SR3") (pin "4") (pinfunction "QE_4") (pintype "tri_state"))
      (node (ref "U3") (pin "30") (pinfunction "2D5_30") (pintype "input"))
      (node (ref "U3") (pin "41") (pinfunction "1D5_41") (pintype "input"))
    )
    (net (code "109") (name "/SR_OUT3_6") (class "Default")
      (node (ref "SR3") (pin "5") (pinfunction "QF_5") (pintype "tri_state"))
      (node (ref "U3") (pin "29") (pinfunction "2D6_29") (pintype "input"))
      (node (ref "U3") (pin "40") (pinfunction "1D6_40") (pintype "input"))
    )
    (net (code "110") (name "/SR_OUT3_7") (class "Default")
      (node (ref "SR3") (pin "6") (pinfunction "QG_6") (pintype "tri_state"))
      (node (ref "U3") (pin "27") (pinfunction "2D7_27") (pintype "input"))
      (node (ref "U3") (pin "38") (pinfunction "1D7_38") (pintype "input"))
    )
    (net (code "111") (name "/SR_OUT3_8") (class "Default")
      (node (ref "SR3") (pin "7") (pinfunction "QH_7") (pintype "tri_state"))
      (node (ref "U3") (pin "26") (pinfunction "2D8_26") (pintype "input"))
      (node (ref "U3") (pin "37") (pinfunction "1D8_37") (pintype "input"))
    )
    (net (code "112") (name "/SR_OUT4_1") (class "Default")
      (node (ref "SR4") (pin "15") (pinfunction "QA_15") (pintype "tri_state"))
      (node (ref "U4") (pin "36") (pinfunction "2D1_36") (pintype "input"))
      (node (ref "U4") (pin "47") (pinfunction "1D1_47") (pintype "input"))
    )
    (net (code "113") (name "/SR_OUT4_2") (class "Default")
      (node (ref "SR4") (pin "1") (pinfunction "QB_1") (pintype "tri_state"))
      (node (ref "U4") (pin "35") (pinfunction "2D2_35") (pintype "input"))
      (node (ref "U4") (pin "46") (pinfunction "1D2_46") (pintype "input"))
    )
    (net (code "114") (name "/SR_OUT4_3") (class "Default")
      (node (ref "SR4") (pin "2") (pinfunction "QC_2") (pintype "tri_state"))
      (node (ref "U4") (pin "33") (pinfunction "2D3_33") (pintype "input"))
      (node (ref "U4") (pin "44") (pinfunction "1D3_44") (pintype "input"))
    )
    (net (code "115") (name "/SR_OUT4_4") (class "Default")
      (node (ref "SR4") (pin "3") (pinfunction "QD_3") (pintype "tri_state"))
      (node (ref "U4") (pin "32") (pinfunction "2D4_32") (pintype "input"))
      (node (ref "U4") (pin "43") (pinfunction "1D4_43") (pintype "input"))
    )
    (net (code "116") (name "/SR_OUT4_5") (class "Default")
      (node (ref "SR4") (pin "4") (pinfunction "QE_4") (pintype "tri_state"))
      (node (ref "U4") (pin "30") (pinfunction "2D5_30") (pintype "input"))
      (node (ref "U4") (pin "41") (pinfunction "1D5_41") (pintype "input"))
    )
    (net (code "117") (name "/SR_OUT4_6") (class "Default")
      (node (ref "SR4") (pin "5") (pinfunction "QF_5") (pintype "tri_state"))
      (node (ref "U4") (pin "29") (pinfunction "2D6_29") (pintype "input"))
      (node (ref "U4") (pin "40") (pinfunction "1D6_40") (pintype "input"))
    )
    (net (code "118") (name "/SR_OUT4_7") (class "Default")
      (node (ref "SR4") (pin "6") (pinfunction "QG_6") (pintype "tri_state"))
      (node (ref "U4") (pin "27") (pinfunction "2D7_27") (pintype "input"))
      (node (ref "U4") (pin "38") (pinfunction "1D7_38") (pintype "input"))
    )
    (net (code "119") (name "/SR_OUT4_8") (class "Default")
      (node (ref "SR4") (pin "7") (pinfunction "QH_7") (pintype "tri_state"))
      (node (ref "U4") (pin "26") (pinfunction "2D8_26") (pintype "input"))
      (node (ref "U4") (pin "37") (pinfunction "1D8_37") (pintype "input"))
    )
    (net (code "120") (name "/SR_OUT5_1") (class "Default")
      (node (ref "SR5") (pin "15") (pinfunction "QA_15") (pintype "tri_state"))
      (node (ref "U5") (pin "36") (pinfunction "2D1_36") (pintype "input"))
      (node (ref "U5") (pin "47") (pinfunction "1D1_47") (pintype "input"))
    )
    (net (code "121") (name "/SR_OUT5_2") (class "Default")
      (node (ref "SR5") (pin "1") (pinfunction "QB_1") (pintype "tri_state"))
      (node (ref "U5") (pin "35") (pinfunction "2D2_35") (pintype "input"))
      (node (ref "U5") (pin "46") (pinfunction "1D2_46") (pintype "input"))
    )
    (net (code "122") (name "/SR_OUT5_3") (class "Default")
      (node (ref "SR5") (pin "2") (pinfunction "QC_2") (pintype "tri_state"))
      (node (ref "U5") (pin "33") (pinfunction "2D3_33") (pintype "input"))
      (node (ref "U5") (pin "44") (pinfunction "1D3_44") (pintype "input"))
    )
    (net (code "123") (name "/SR_OUT5_4") (class "Default")
      (node (ref "SR5") (pin "3") (pinfunction "QD_3") (pintype "tri_state"))
      (node (ref "U5") (pin "32") (pinfunction "2D4_32") (pintype "input"))
      (node (ref "U5") (pin "43") (pinfunction "1D4_43") (pintype "input"))
    )
    (net (code "124") (name "/SR_OUT5_5") (class "Default")
      (node (ref "SR5") (pin "4") (pinfunction "QE_4") (pintype "tri_state"))
      (node (ref "U5") (pin "30") (pinfunction "2D5_30") (pintype "input"))
      (node (ref "U5") (pin "41") (pinfunction "1D5_41") (pintype "input"))
    )
    (net (code "125") (name "/SR_OUT5_6") (class "Default")
      (node (ref "SR5") (pin "5") (pinfunction "QF_5") (pintype "tri_state"))
      (node (ref "U5") (pin "29") (pinfunction "2D6_29") (pintype "input"))
      (node (ref "U5") (pin "40") (pinfunction "1D6_40") (pintype "input"))
    )
    (net (code "126") (name "/SR_OUT5_7") (class "Default")
      (node (ref "SR5") (pin "6") (pinfunction "QG_6") (pintype "tri_state"))
      (node (ref "U5") (pin "27") (pinfunction "2D7_27") (pintype "input"))
      (node (ref "U5") (pin "38") (pinfunction "1D7_38") (pintype "input"))
    )
    (net (code "127") (name "/SR_OUT5_8") (class "Default")
      (node (ref "SR5") (pin "7") (pinfunction "QH_7") (pintype "tri_state"))
      (node (ref "U5") (pin "26") (pinfunction "2D8_26") (pintype "input"))
      (node (ref "U5") (pin "37") (pinfunction "1D8_37") (pintype "input"))
    )
    (net (code "128") (name "/VCC_LATCH") (class "Default")
      (node (ref "JP10") (pin "2") (pinfunction "2_2") (pintype "passive"))
      (node (ref "JP7") (pin "2") (pinfunction "2_2") (pintype "passive"))
      (node (ref "JP8") (pin "2") (pinfunction "2_2") (pintype "passive"))
      (node (ref "JP9") (pin "2") (pinfunction "2_2") (pintype "passive"))
      (node (ref "U1") (pin "18") (pinfunction "1_VCC_18") (pintype "power_in"))
      (node (ref "U1") (pin "31") (pinfunction "2_VCC_31") (pintype "power_in"))
      (node (ref "U1") (pin "42") (pinfunction "3_VCC_42") (pintype "power_in"))
      (node (ref "U1") (pin "7") (pinfunction "4_VCC_7") (pintype "power_in"))
      (node (ref "U2") (pin "18") (pinfunction "1_VCC_18") (pintype "power_in"))
      (node (ref "U2") (pin "31") (pinfunction "2_VCC_31") (pintype "power_in"))
      (node (ref "U2") (pin "42") (pinfunction "3_VCC_42") (pintype "power_in"))
      (node (ref "U2") (pin "7") (pinfunction "4_VCC_7") (pintype "power_in"))
      (node (ref "U3") (pin "18") (pinfunction "1_VCC_18") (pintype "power_in"))
      (node (ref "U3") (pin "31") (pinfunction "2_VCC_31") (pintype "power_in"))
      (node (ref "U3") (pin "42") (pinfunction "3_VCC_42") (pintype "power_in"))
      (node (ref "U3") (pin "7") (pinfunction "4_VCC_7") (pintype "power_in"))
      (node (ref "U4") (pin "18") (pinfunction "1_VCC_18") (pintype "power_in"))
      (node (ref "U4") (pin "31") (pinfunction "2_VCC_31") (pintype "power_in"))
      (node (ref "U4") (pin "42") (pinfunction "3_VCC_42") (pintype "power_in"))
      (node (ref "U4") (pin "7") (pinfunction "4_VCC_7") (pintype "power_in"))
      (node (ref "U5") (pin "18") (pinfunction "1_VCC_18") (pintype "power_in"))
      (node (ref "U5") (pin "31") (pinfunction "2_VCC_31") (pintype "power_in"))
      (node (ref "U5") (pin "42") (pinfunction "3_VCC_42") (pintype "power_in"))
      (node (ref "U5") (pin "7") (pinfunction "4_VCC_7") (pintype "power_in"))
    )
    (net (code "129") (name "/VCC_SR") (class "Default")
      (node (ref "JP10") (pin "1") (pinfunction "1_1") (pintype "passive"))
      (node (ref "JP7") (pin "1") (pinfunction "1_1") (pintype "passive"))
      (node (ref "JP8") (pin "1") (pinfunction "1_1") (pintype "passive"))
      (node (ref "JP9") (pin "1") (pinfunction "1_1") (pintype "passive"))
      (node (ref "SR1") (pin "10") (pinfunction "~{SCLR}_10") (pintype "input"))
      (node (ref "SR1") (pin "16") (pinfunction "VCC_16") (pintype "power_in"))
      (node (ref "SR2") (pin "10") (pinfunction "~{SCLR}_10") (pintype "input"))
      (node (ref "SR2") (pin "16") (pinfunction "VCC_16") (pintype "power_in"))
      (node (ref "SR3") (pin "10") (pinfunction "~{SCLR}_10") (pintype "input"))
      (node (ref "SR3") (pin "16") (pinfunction "VCC_16") (pintype "power_in"))
      (node (ref "SR4") (pin "10") (pinfunction "~{SCLR}_10") (pintype "input"))
      (node (ref "SR4") (pin "16") (pinfunction "VCC_16") (pintype "power_in"))
      (node (ref "SR5") (pin "10") (pinfunction "~{SCLR}_10") (pintype "input"))
      (node (ref "SR5") (pin "16") (pinfunction "VCC_16") (pintype "power_in"))
    )
    (net (code "130") (name "Net-(LED1-PadA)") (class "Default")
      (node (ref "LED1") (pin "A") (pinfunction "A_A") (pintype "passive"))
      (node (ref "R1") (pin "2") (pinfunction "2_2") (pintype "passive"))
    )
    (net (code "131") (name "Net-(LED2-PadA)") (class "Default")
      (node (ref "LED2") (pin "A") (pinfunction "A_A") (pintype "passive"))
      (node (ref "R2") (pin "2") (pinfunction "2_2") (pintype "passive"))
    )
    (net (code "132") (name "Net-(LED3-PadA)") (class "Default")
      (node (ref "LED3") (pin "A") (pinfunction "A_A") (pintype "passive"))
      (node (ref "R3") (pin "2") (pinfunction "2_2") (pintype "passive"))
    )
    (net (code "133") (name "Net-(LED4-PadA)") (class "Default")
      (node (ref "LED4") (pin "A") (pinfunction "A_A") (pintype "passive"))
      (node (ref "R4") (pin "2") (pinfunction "2_2") (pintype "passive"))
    )
    (net (code "134") (name "Net-(LED5-PadA)") (class "Default")
      (node (ref "LED5") (pin "A") (pinfunction "A_A") (pintype "passive"))
      (node (ref "R5") (pin "2") (pinfunction "2_2") (pintype "passive"))
    )
    (net (code "135") (name "Net-(LED6-PadA)") (class "Default")
      (node (ref "LED6") (pin "A") (pinfunction "A_A") (pintype "passive"))
      (node (ref "R6") (pin "2") (pinfunction "2_2") (pintype "passive"))
    )
    (net (code "136") (name "Net-(LED7-PadA)") (class "Default")
      (node (ref "LED7") (pin "A") (pinfunction "A_A") (pintype "passive"))
      (node (ref "R7") (pin "2") (pinfunction "2_2") (pintype "passive"))
    )
    (net (code "137") (name "Net-(LED8-PadA)") (class "Default")
      (node (ref "LED8") (pin "A") (pinfunction "A_A") (pintype "passive"))
      (node (ref "R8") (pin "2") (pinfunction "2_2") (pintype "passive"))
    )
    (net (code "138") (name "Net-(SR1-QH')") (class "Default")
      (node (ref "SR1") (pin "9") (pinfunction "QH'_9") (pintype "tri_state"))
      (node (ref "SR2") (pin "14") (pinfunction "SER_14") (pintype "input"))
    )
    (net (code "139") (name "Net-(SR2-QH')") (class "Default")
      (node (ref "SR2") (pin "9") (pinfunction "QH'_9") (pintype "tri_state"))
      (node (ref "SR3") (pin "14") (pinfunction "SER_14") (pintype "input"))
    )
    (net (code "140") (name "Net-(SR3-QH')") (class "Default")
      (node (ref "SR3") (pin "9") (pinfunction "QH'_9") (pintype "tri_state"))
      (node (ref "SR4") (pin "14") (pinfunction "SER_14") (pintype "input"))
    )
    (net (code "141") (name "Net-(SR4-QH')") (class "Default")
      (node (ref "SR4") (pin "9") (pinfunction "QH'_9") (pintype "tri_state"))
      (node (ref "SR5") (pin "14") (pinfunction "SER_14") (pintype "input"))
    )
  )
)
